# working.net
KiCad netlist of a schematic drawn in EAGLE
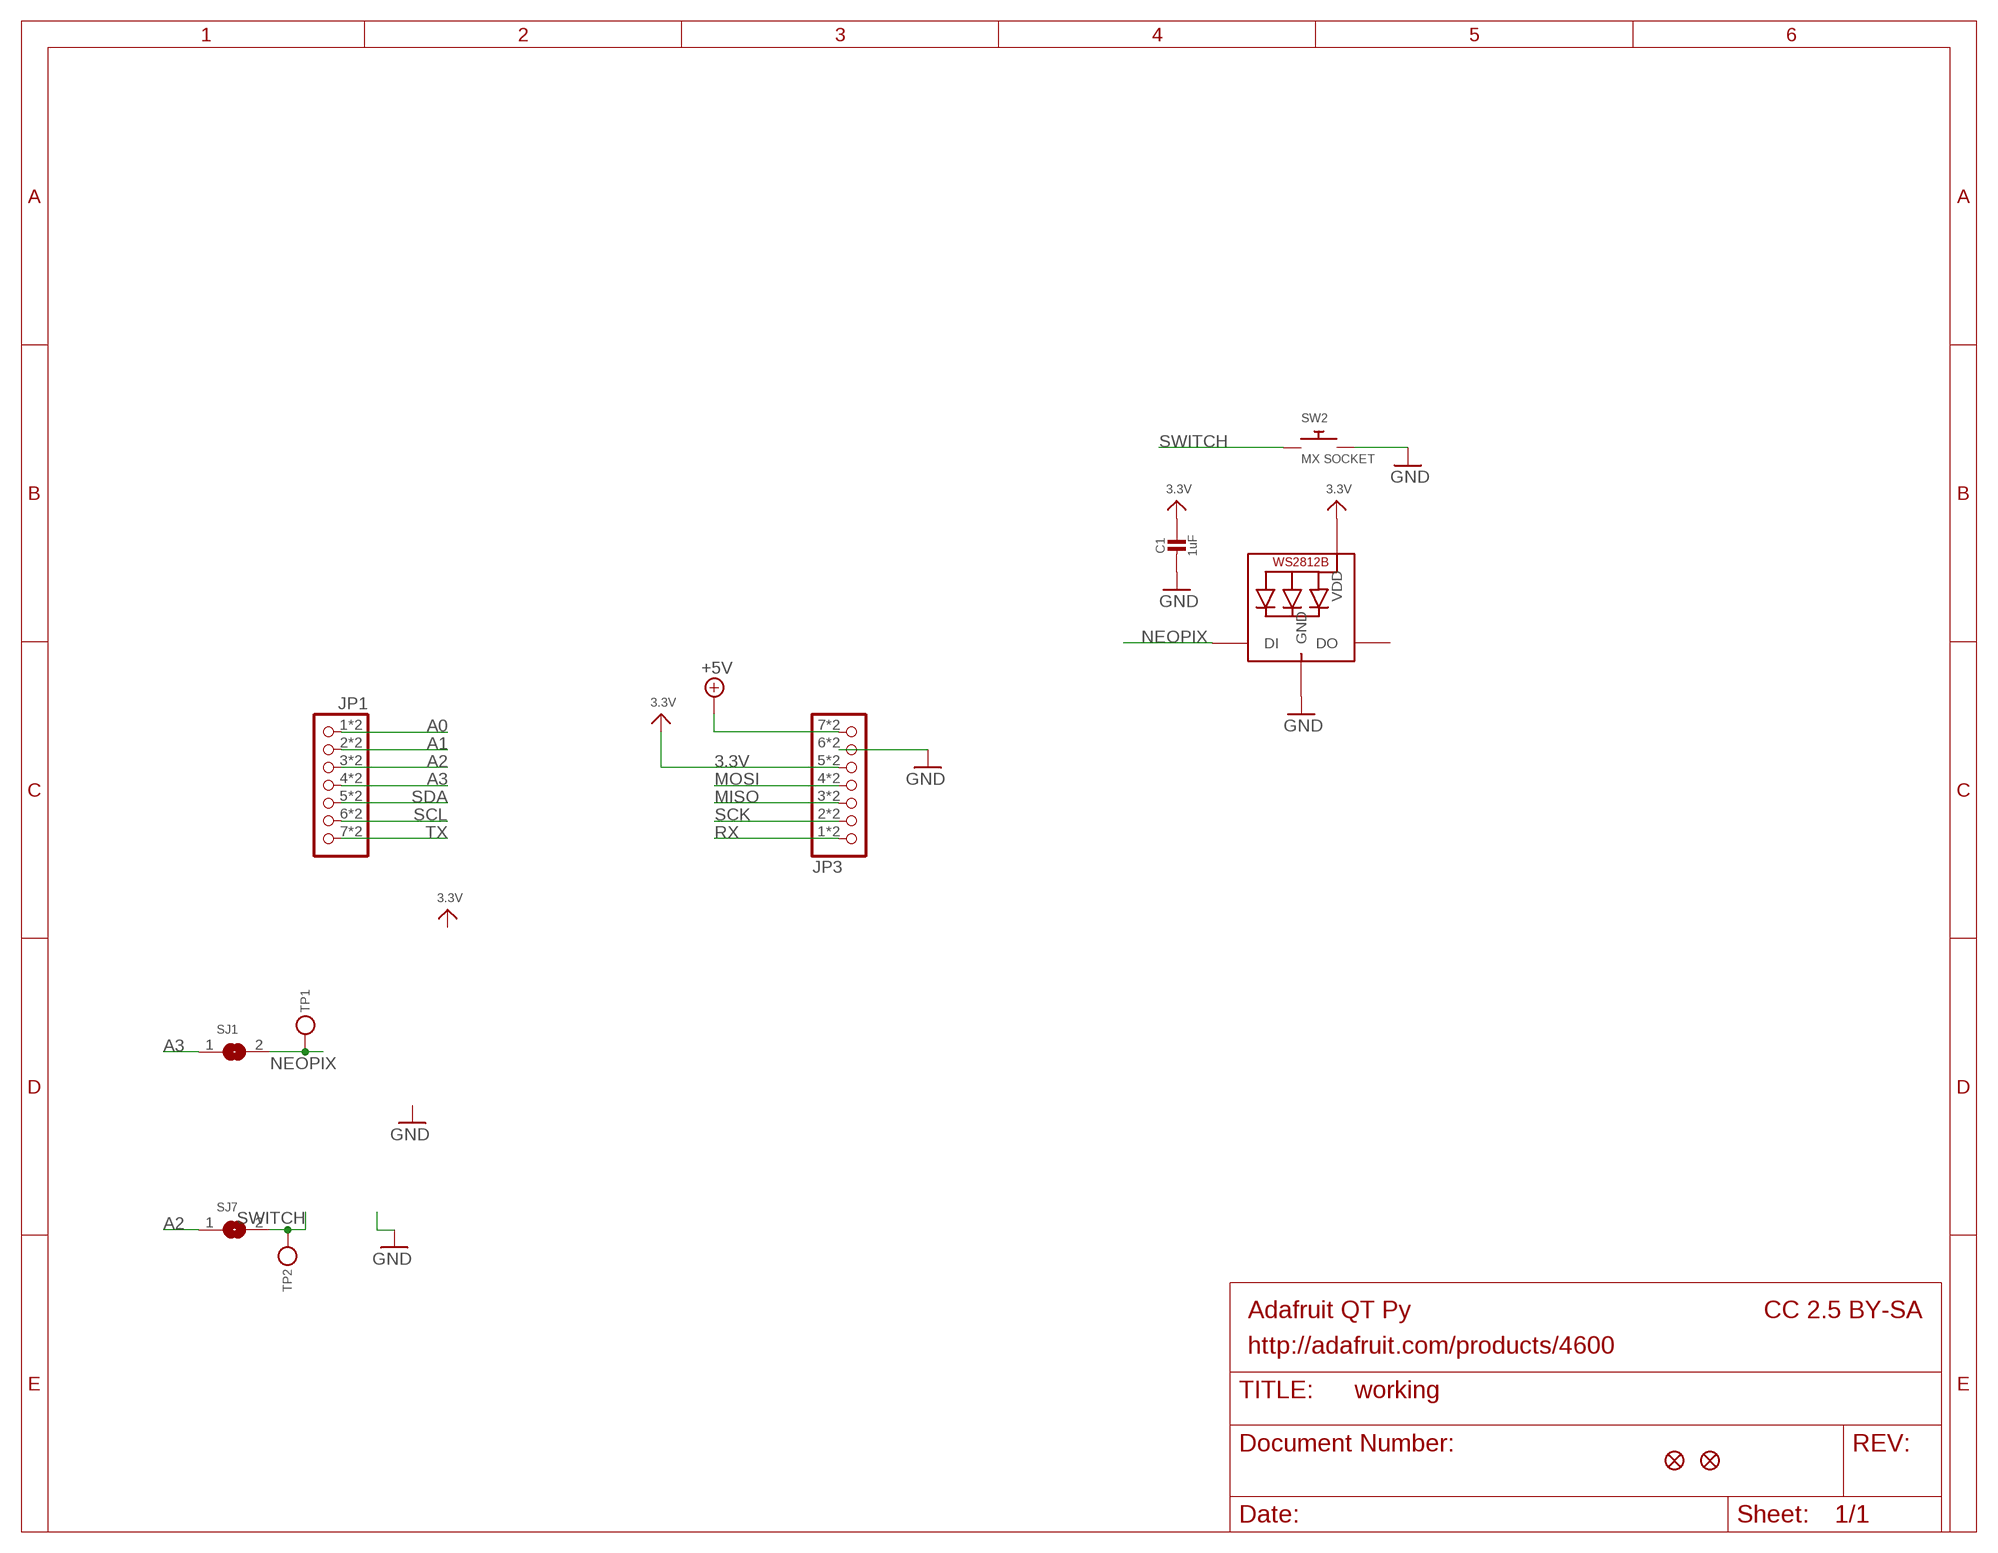
[diagram p0: schematic, sheet 1]

(export (version "E")
  (design (tool "Eeschema 10.0.6"))
  (components
    (comp (ref "C1")
      (value "1uF")
      (footprint "eagle-import:0603-NO")
      (libsource (lib "eagle-import") (part "CAP_CERAMIC0603_NO"))
    )
    (comp (ref "JP1")
      (value "HEADER-1X7_CASTEL")
      (footprint "eagle-import:1X07_CASTEL")
      (libsource (lib "eagle-import") (part "HEADER-1X7_CASTEL"))
    )
    (comp (ref "JP3")
      (value "HEADER-1X7_CASTEL")
      (footprint "eagle-import:1X07_CASTEL")
      (libsource (lib "eagle-import") (part "HEADER-1X7_CASTEL"))
    )
    (comp (ref "LED2")
      (value "WS2812B_SK6812E")
      (footprint "eagle-import:NEO3535_REVERSE")
      (libsource (lib "eagle-import") (part "WS2812B_SK6812E"))
    )
    (comp (ref "SJ1")
      (value "SOLDERJUMPERCLOSED")
      (footprint "eagle-import:SOLDERJUMPER_CLOSEDWIRE")
      (libsource (lib "eagle-import") (part "SOLDERJUMPERCLOSED"))
    )
    (comp (ref "SJ7")
      (value "SOLDERJUMPERCLOSED")
      (footprint "eagle-import:SOLDERJUMPER_CLOSEDWIRE")
      (libsource (lib "eagle-import") (part "SOLDERJUMPERCLOSED"))
    )
    (comp (ref "SW2")
      (value "MX SOCKET")
      (footprint "eagle-import:KAILH_SOCKET")
      (fields (field (name "XOFFSET") "-.75"))
      (libsource (lib "eagle-import") (part "SWITCH_PUSHBUTTON_KAILH_SOCKET"))
    )
    (comp (ref "TP1")
      (value "TESTPOINT1.5X2.0MM_NOCREAM")
      (footprint "eagle-import:PAD-1.5X2.0")
      (libsource (lib "eagle-import") (part "TESTPOINT1.5X2.0MM_NOCREAM"))
    )
    (comp (ref "TP2")
      (value "TESTPOINT1.5X2.0MM_NOCREAM")
      (footprint "eagle-import:PAD-1.5X2.0")
      (libsource (lib "eagle-import") (part "TESTPOINT1.5X2.0MM_NOCREAM"))
    )
    (comp (ref "U$6")
      (value "FIDUCIAL_1MM")
      (footprint "eagle-import:FIDUCIAL_1MM")
      (libsource (lib "eagle-import") (part "FIDUCIAL_1MM"))
    )
    (comp (ref "U$8")
      (value "FIDUCIAL_1MM")
      (footprint "eagle-import:FIDUCIAL_1MM")
      (libsource (lib "eagle-import") (part "FIDUCIAL_1MM"))
    )
  )
  (nets
    (net (code "1") (name "+5V") (class "Default")
      (node (ref "JP3") (pin "7") (pinfunction "7_7") (pintype "passive"))
      (node (ref "JP3") (pin "7C") (pinfunction "7_7C") (pintype "passive"))
    )
    (net (code "2") (name "/A0") (class "Default")
      (node (ref "JP1") (pin "1") (pinfunction "1_1") (pintype "passive"))
      (node (ref "JP1") (pin "1C") (pinfunction "1_1C") (pintype "passive"))
    )
    (net (code "3") (name "/A1") (class "Default")
      (node (ref "JP1") (pin "2") (pinfunction "2_2") (pintype "passive"))
      (node (ref "JP1") (pin "2C") (pinfunction "2_2C") (pintype "passive"))
    )
    (net (code "4") (name "/A2") (class "Default")
      (node (ref "JP1") (pin "3") (pinfunction "3_3") (pintype "passive"))
      (node (ref "JP1") (pin "3C") (pinfunction "3_3C") (pintype "passive"))
      (node (ref "SJ7") (pin "1") (pinfunction "1_1") (pintype "passive"))
    )
    (net (code "5") (name "/A3") (class "Default")
      (node (ref "JP1") (pin "4") (pinfunction "4_4") (pintype "passive"))
      (node (ref "JP1") (pin "4C") (pinfunction "4_4C") (pintype "passive"))
      (node (ref "SJ1") (pin "1") (pinfunction "1_1") (pintype "passive"))
    )
    (net (code "6") (name "/MISO") (class "Default")
      (node (ref "JP3") (pin "3") (pinfunction "3_3") (pintype "passive"))
      (node (ref "JP3") (pin "3C") (pinfunction "3_3C") (pintype "passive"))
    )
    (net (code "7") (name "/MOSI") (class "Default")
      (node (ref "JP3") (pin "4") (pinfunction "4_4") (pintype "passive"))
      (node (ref "JP3") (pin "4C") (pinfunction "4_4C") (pintype "passive"))
    )
    (net (code "8") (name "/NEOPIX") (class "Default")
      (node (ref "LED2") (pin "4-DIN") (pinfunction "DI_4-DIN") (pintype "input"))
      (node (ref "SJ1") (pin "2") (pinfunction "2_2") (pintype "passive"))
      (node (ref "TP1") (pin "P$1") (pinfunction "P$1_P$1") (pintype "bidirectional"))
    )
    (net (code "9") (name "/RX") (class "Default")
      (node (ref "JP3") (pin "1") (pinfunction "1_1") (pintype "passive"))
      (node (ref "JP3") (pin "1C") (pinfunction "1_1C") (pintype "passive"))
    )
    (net (code "10") (name "/SCK") (class "Default")
      (node (ref "JP3") (pin "2") (pinfunction "2_2") (pintype "passive"))
      (node (ref "JP3") (pin "2C") (pinfunction "2_2C") (pintype "passive"))
    )
    (net (code "11") (name "/SCL") (class "Default")
      (node (ref "JP1") (pin "6") (pinfunction "6_6") (pintype "passive"))
      (node (ref "JP1") (pin "6C") (pinfunction "6_6C") (pintype "passive"))
    )
    (net (code "12") (name "/SDA") (class "Default")
      (node (ref "JP1") (pin "5") (pinfunction "5_5") (pintype "passive"))
      (node (ref "JP1") (pin "5C") (pinfunction "5_5C") (pintype "passive"))
    )
    (net (code "13") (name "/SWITCH") (class "Default")
      (node (ref "SJ7") (pin "2") (pinfunction "2_2") (pintype "passive"))
      (node (ref "SW2") (pin "1") (pinfunction "P$1_1") (pintype "passive"))
      (node (ref "TP2") (pin "P$1") (pinfunction "P$1_P$1") (pintype "bidirectional"))
    )
    (net (code "14") (name "/TX") (class "Default")
      (node (ref "JP1") (pin "7") (pinfunction "7_7") (pintype "passive"))
      (node (ref "JP1") (pin "7C") (pinfunction "7_7C") (pintype "passive"))
    )
    (net (code "15") (name "3.3V") (class "Default")
      (node (ref "C1") (pin "1") (pinfunction "1_1") (pintype "passive"))
      (node (ref "JP3") (pin "5") (pinfunction "5_5") (pintype "passive"))
      (node (ref "JP3") (pin "5C") (pinfunction "5_5C") (pintype "passive"))
      (node (ref "LED2") (pin "1-VDD") (pinfunction "VDD_1-VDD") (pintype "power_in"))
    )
    (net (code "16") (name "GND") (class "Default")
      (node (ref "C1") (pin "2") (pinfunction "2_2") (pintype "passive"))
      (node (ref "JP3") (pin "6") (pinfunction "6_6") (pintype "passive"))
      (node (ref "JP3") (pin "6C") (pinfunction "6_6C") (pintype "passive"))
      (node (ref "LED2") (pin "3-GND") (pinfunction "GND_3-GND") (pintype "power_in"))
      (node (ref "SW2") (pin "2") (pinfunction "P$2_2") (pintype "passive"))
    )
    (net (code "17") (name "unconnected-(LED2-DO-Pad2-DOUT)") (class "Default")
      (node (ref "LED2") (pin "2-DOUT") (pinfunction "DO_2-DOUT") (pintype "output"))
    )
  )
)
